# TD4Peripheral.net
KiCad netlist of a schematic drawn in EAGLE
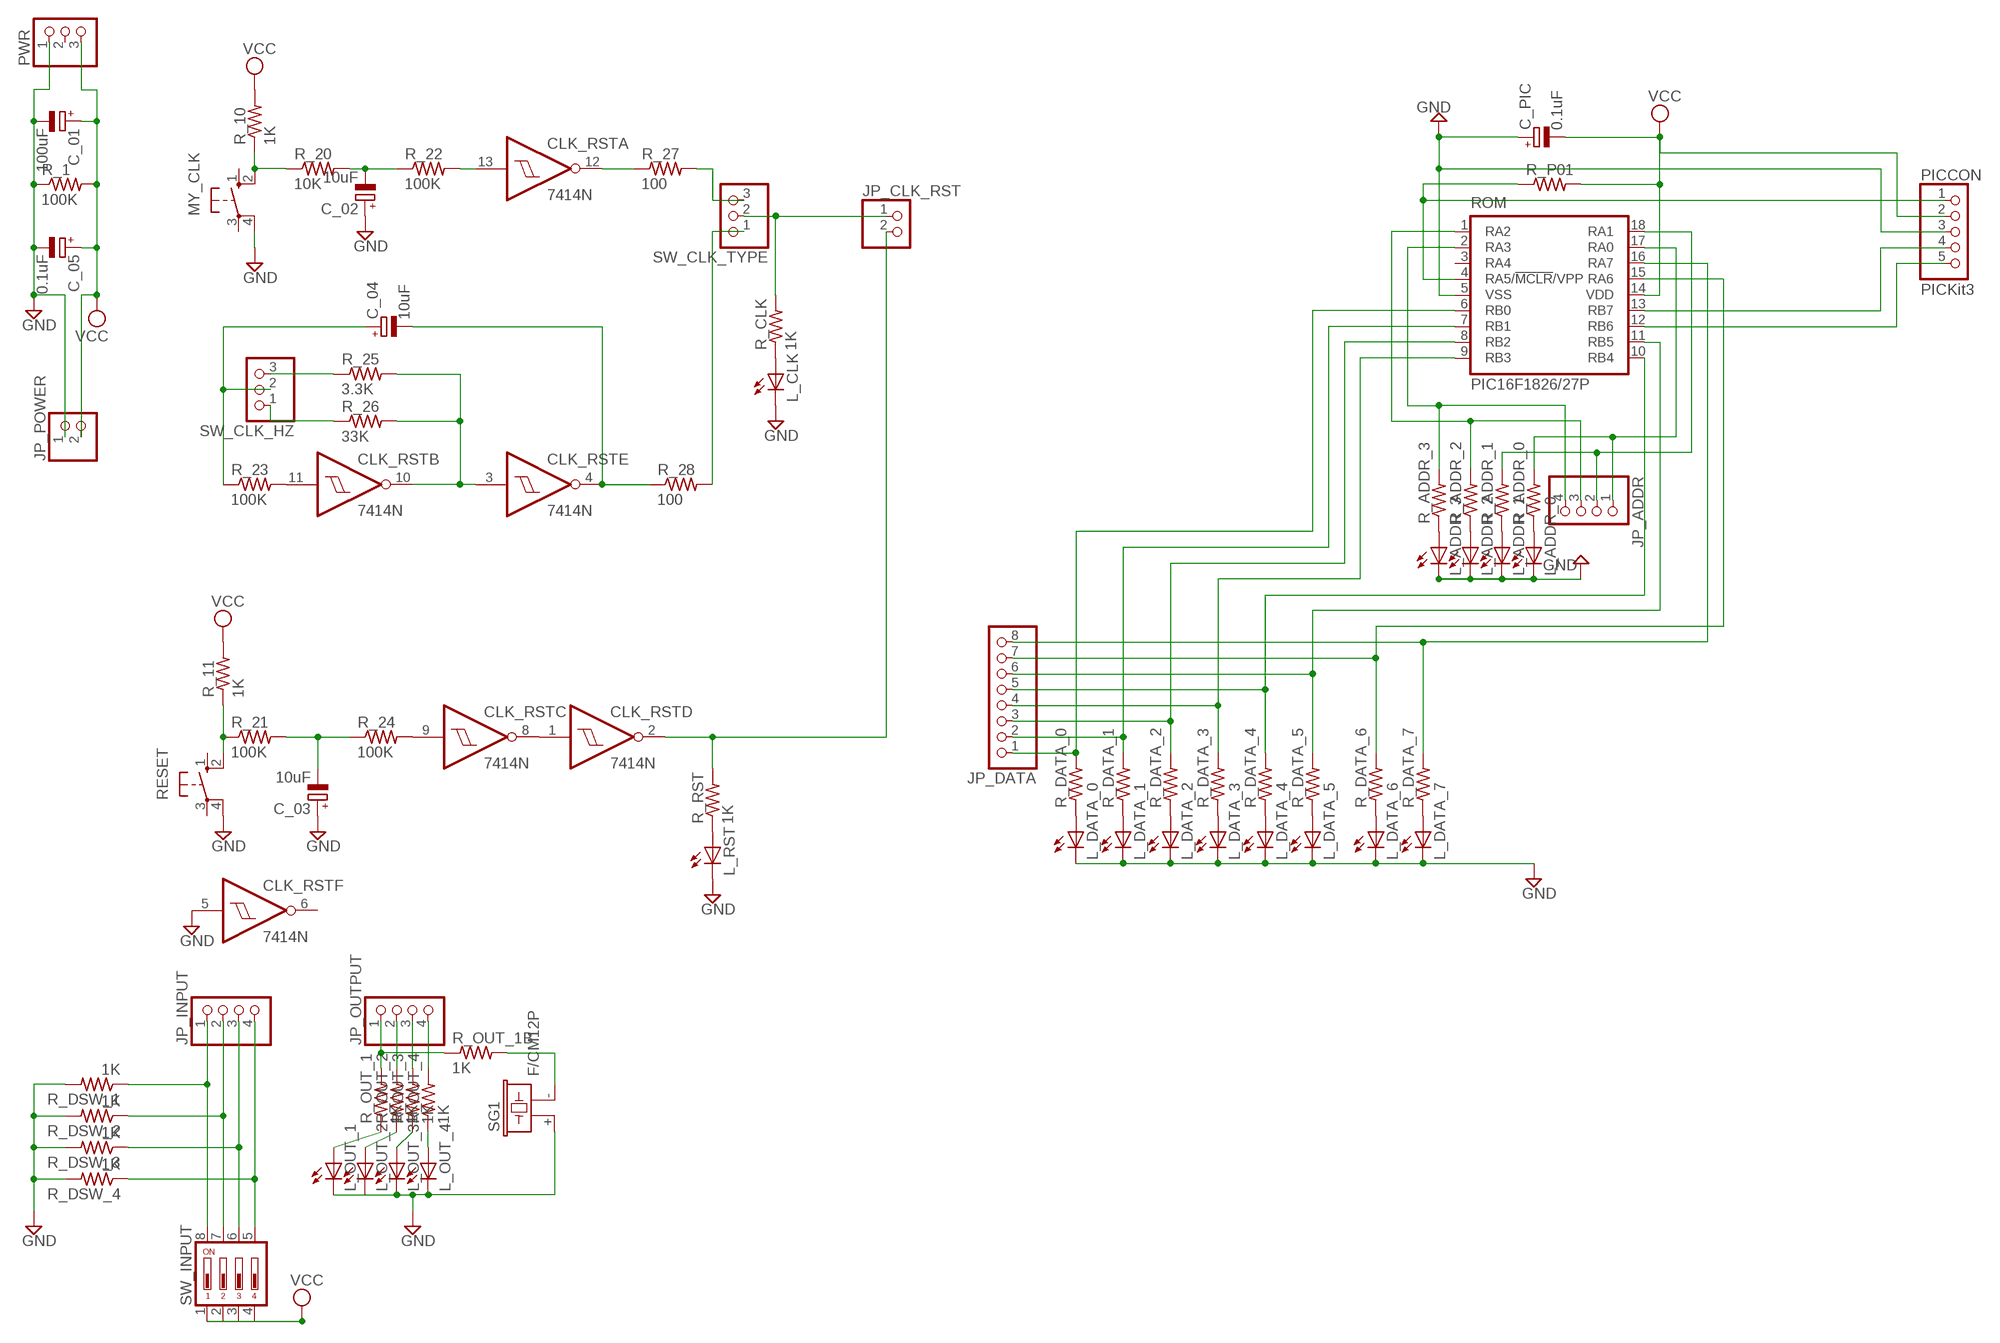
[diagram p0: schematic, sheet 1]

(export (version "E")
  (design (tool "Eeschema 10.0.6"))
  (components
    (comp (ref "CLK_RST")
      (value "7414N")
      (footprint "eagle-import:DIL14")
      (libsource (lib "eagle-import") (part "7414N"))
    )
    (comp (ref "C_01")
      (value "100uF")
      (footprint "eagle-import:E2-5")
      (libsource (lib "eagle-import") (part "CPOL-EUE2-5"))
    )
    (comp (ref "C_02")
      (value "10uF")
      (footprint "eagle-import:E2-5")
      (libsource (lib "eagle-import") (part "CPOL-EUE2-5"))
    )
    (comp (ref "C_03")
      (value "10uF")
      (footprint "eagle-import:E2-5")
      (libsource (lib "eagle-import") (part "CPOL-EUE2-5"))
    )
    (comp (ref "C_04")
      (value "10uF")
      (footprint "eagle-import:E2-5")
      (libsource (lib "eagle-import") (part "CPOL-EUE2-5"))
    )
    (comp (ref "C_05")
      (value "0.1uF")
      (footprint "eagle-import:E2-5")
      (libsource (lib "eagle-import") (part "CPOL-EUE2-5"))
    )
    (comp (ref "C_PIC")
      (value "0.1uF")
      (footprint "eagle-import:E2-5")
      (libsource (lib "eagle-import") (part "CPOL-EUE2-5"))
    )
    (comp (ref "JP_ADDR")
      (value "PINHD-1X4")
      (footprint "eagle-import:1X04")
      (libsource (lib "eagle-import") (part "PINHD-1X4"))
    )
    (comp (ref "JP_CLK_RST")
      (value "PINHD-1X2")
      (footprint "eagle-import:1X02")
      (libsource (lib "eagle-import") (part "PINHD-1X2"))
    )
    (comp (ref "JP_DATA")
      (value "PINHD-1X8")
      (footprint "eagle-import:1X08")
      (libsource (lib "eagle-import") (part "PINHD-1X8"))
    )
    (comp (ref "JP_INPUT")
      (value "PINHD-1X4")
      (footprint "eagle-import:1X04")
      (libsource (lib "eagle-import") (part "PINHD-1X4"))
    )
    (comp (ref "JP_OUTPUT")
      (value "PINHD-1X4")
      (footprint "eagle-import:1X04")
      (libsource (lib "eagle-import") (part "PINHD-1X4"))
    )
    (comp (ref "JP_POWER")
      (value "PINHD-1X2")
      (footprint "eagle-import:1X02")
      (libsource (lib "eagle-import") (part "PINHD-1X2"))
    )
    (comp (ref "L_ADDR_0")
      (value "LED5MM")
      (footprint "eagle-import:LED5MM")
      (libsource (lib "eagle-import") (part "LED5MM"))
    )
    (comp (ref "L_ADDR_1")
      (value "LED5MM")
      (footprint "eagle-import:LED5MM")
      (libsource (lib "eagle-import") (part "LED5MM"))
    )
    (comp (ref "L_ADDR_2")
      (value "LED5MM")
      (footprint "eagle-import:LED5MM")
      (libsource (lib "eagle-import") (part "LED5MM"))
    )
    (comp (ref "L_ADDR_3")
      (value "LED5MM")
      (footprint "eagle-import:LED5MM")
      (libsource (lib "eagle-import") (part "LED5MM"))
    )
    (comp (ref "L_CLK")
      (value "LED5MM")
      (footprint "eagle-import:LED5MM")
      (libsource (lib "eagle-import") (part "LED5MM"))
    )
    (comp (ref "L_DATA_0")
      (value "LED5MM")
      (footprint "eagle-import:LED5MM")
      (libsource (lib "eagle-import") (part "LED5MM"))
    )
    (comp (ref "L_DATA_1")
      (value "LED5MM")
      (footprint "eagle-import:LED5MM")
      (libsource (lib "eagle-import") (part "LED5MM"))
    )
    (comp (ref "L_DATA_2")
      (value "LED5MM")
      (footprint "eagle-import:LED5MM")
      (libsource (lib "eagle-import") (part "LED5MM"))
    )
    (comp (ref "L_DATA_3")
      (value "LED5MM")
      (footprint "eagle-import:LED5MM")
      (libsource (lib "eagle-import") (part "LED5MM"))
    )
    (comp (ref "L_DATA_4")
      (value "LED5MM")
      (footprint "eagle-import:LED5MM")
      (libsource (lib "eagle-import") (part "LED5MM"))
    )
    (comp (ref "L_DATA_5")
      (value "LED5MM")
      (footprint "eagle-import:LED5MM")
      (libsource (lib "eagle-import") (part "LED5MM"))
    )
    (comp (ref "L_DATA_6")
      (value "LED5MM")
      (footprint "eagle-import:LED5MM")
      (libsource (lib "eagle-import") (part "LED5MM"))
    )
    (comp (ref "L_DATA_7")
      (value "LED5MM")
      (footprint "eagle-import:LED5MM")
      (libsource (lib "eagle-import") (part "LED5MM"))
    )
    (comp (ref "L_OUT_1")
      (value "LED5MM")
      (footprint "eagle-import:LED5MM")
      (libsource (lib "eagle-import") (part "LED5MM"))
    )
    (comp (ref "L_OUT_2")
      (value "LED5MM")
      (footprint "eagle-import:LED5MM")
      (libsource (lib "eagle-import") (part "LED5MM"))
    )
    (comp (ref "L_OUT_3")
      (value "LED5MM")
      (footprint "eagle-import:LED5MM")
      (libsource (lib "eagle-import") (part "LED5MM"))
    )
    (comp (ref "L_OUT_4")
      (value "LED5MM")
      (footprint "eagle-import:LED5MM")
      (libsource (lib "eagle-import") (part "LED5MM"))
    )
    (comp (ref "L_RST")
      (value "LED5MM")
      (footprint "eagle-import:LED5MM")
      (libsource (lib "eagle-import") (part "LED5MM"))
    )
    (comp (ref "MY_CLK")
      (value "10-XX")
      (footprint "eagle-import:B3F-10XX")
      (fields (field (name "MPN") "B3F-1000"))
      (libsource (lib "eagle-import") (part "10-XX"))
    )
    (comp (ref "PICCON")
      (value "PICKit3")
      (footprint "eagle-import:1X05")
      (libsource (lib "eagle-import") (part "PINHD-1X5"))
    )
    (comp (ref "PWR")
      (value "PINHD-1X3")
      (footprint "eagle-import:1X03")
      (libsource (lib "eagle-import") (part "PINHD-1X3"))
    )
    (comp (ref "RESET")
      (value "10-XX")
      (footprint "eagle-import:B3F-10XX")
      (fields (field (name "MPN") "B3F-1000"))
      (libsource (lib "eagle-import") (part "10-XX"))
    )
    (comp (ref "ROM")
      (value "PIC16F1826/27P")
      (footprint "eagle-import:DIL18")
      (libsource (lib "eagle-import") (part "PIC16F1826/27P"))
    )
    (comp (ref "R_1")
      (value "100K")
      (footprint "eagle-import:0204_7")
      (libsource (lib "eagle-import") (part "R-US_0204/7"))
    )
    (comp (ref "R_10")
      (value "1K")
      (footprint "eagle-import:0204_7")
      (libsource (lib "eagle-import") (part "R-US_0204/7"))
    )
    (comp (ref "R_11")
      (value "1K")
      (footprint "eagle-import:0204_7")
      (libsource (lib "eagle-import") (part "R-US_0204/7"))
    )
    (comp (ref "R_20")
      (value "10K")
      (footprint "eagle-import:0204_7")
      (libsource (lib "eagle-import") (part "R-US_0204/7"))
    )
    (comp (ref "R_21")
      (value "100K")
      (footprint "eagle-import:0204_7")
      (libsource (lib "eagle-import") (part "R-US_0204/7"))
    )
    (comp (ref "R_22")
      (value "100K")
      (footprint "eagle-import:0204_7")
      (libsource (lib "eagle-import") (part "R-US_0204/7"))
    )
    (comp (ref "R_23")
      (value "100K")
      (footprint "eagle-import:0204_7")
      (libsource (lib "eagle-import") (part "R-US_0204/7"))
    )
    (comp (ref "R_24")
      (value "100K")
      (footprint "eagle-import:0204_7")
      (libsource (lib "eagle-import") (part "R-US_0204/7"))
    )
    (comp (ref "R_25")
      (value "3.3K")
      (footprint "eagle-import:0204_7")
      (libsource (lib "eagle-import") (part "R-US_0204/7"))
    )
    (comp (ref "R_26")
      (value "33K")
      (footprint "eagle-import:0204_7")
      (libsource (lib "eagle-import") (part "R-US_0204/7"))
    )
    (comp (ref "R_27")
      (value "100")
      (footprint "eagle-import:0204_7")
      (libsource (lib "eagle-import") (part "R-US_0204/7"))
    )
    (comp (ref "R_28")
      (value "100")
      (footprint "eagle-import:0204_7")
      (libsource (lib "eagle-import") (part "R-US_0204/7"))
    )
    (comp (ref "R_ADDR_0")
      (value "R-US_0204/7")
      (footprint "eagle-import:0204_7")
      (libsource (lib "eagle-import") (part "R-US_0204/7"))
    )
    (comp (ref "R_ADDR_1")
      (value "R-US_0204/7")
      (footprint "eagle-import:0204_7")
      (libsource (lib "eagle-import") (part "R-US_0204/7"))
    )
    (comp (ref "R_ADDR_2")
      (value "R-US_0204/7")
      (footprint "eagle-import:0204_7")
      (libsource (lib "eagle-import") (part "R-US_0204/7"))
    )
    (comp (ref "R_ADDR_3")
      (value "R-US_0204/7")
      (footprint "eagle-import:0204_7")
      (libsource (lib "eagle-import") (part "R-US_0204/7"))
    )
    (comp (ref "R_CLK")
      (value "1K")
      (footprint "eagle-import:0204_7")
      (libsource (lib "eagle-import") (part "R-US_0204/7"))
    )
    (comp (ref "R_DATA_0")
      (value "R-US_0204/7")
      (footprint "eagle-import:0204_7")
      (libsource (lib "eagle-import") (part "R-US_0204/7"))
    )
    (comp (ref "R_DATA_1")
      (value "R-US_0204/7")
      (footprint "eagle-import:0204_7")
      (libsource (lib "eagle-import") (part "R-US_0204/7"))
    )
    (comp (ref "R_DATA_2")
      (value "R-US_0204/7")
      (footprint "eagle-import:0204_7")
      (libsource (lib "eagle-import") (part "R-US_0204/7"))
    )
    (comp (ref "R_DATA_3")
      (value "R-US_0204/7")
      (footprint "eagle-import:0204_7")
      (libsource (lib "eagle-import") (part "R-US_0204/7"))
    )
    (comp (ref "R_DATA_4")
      (value "R-US_0204/7")
      (footprint "eagle-import:0204_7")
      (libsource (lib "eagle-import") (part "R-US_0204/7"))
    )
    (comp (ref "R_DATA_5")
      (value "R-US_0204/7")
      (footprint "eagle-import:0204_7")
      (libsource (lib "eagle-import") (part "R-US_0204/7"))
    )
    (comp (ref "R_DATA_6")
      (value "R-US_0204/7")
      (footprint "eagle-import:0204_7")
      (libsource (lib "eagle-import") (part "R-US_0204/7"))
    )
    (comp (ref "R_DATA_7")
      (value "R-US_0204/7")
      (footprint "eagle-import:0204_7")
      (libsource (lib "eagle-import") (part "R-US_0204/7"))
    )
    (comp (ref "R_DSW_1")
      (value "1K")
      (footprint "eagle-import:0204_7")
      (libsource (lib "eagle-import") (part "R-US_0204/7"))
    )
    (comp (ref "R_DSW_2")
      (value "1K")
      (footprint "eagle-import:0204_7")
      (libsource (lib "eagle-import") (part "R-US_0204/7"))
    )
    (comp (ref "R_DSW_3")
      (value "1K")
      (footprint "eagle-import:0204_7")
      (libsource (lib "eagle-import") (part "R-US_0204/7"))
    )
    (comp (ref "R_DSW_4")
      (value "1K")
      (footprint "eagle-import:0204_7")
      (libsource (lib "eagle-import") (part "R-US_0204/7"))
    )
    (comp (ref "R_OUT_1")
      (value "1K")
      (footprint "eagle-import:0204_7")
      (libsource (lib "eagle-import") (part "R-US_0204/7"))
    )
    (comp (ref "R_OUT_1B")
      (value "1K")
      (footprint "eagle-import:0204_7")
      (libsource (lib "eagle-import") (part "R-US_0204/7"))
    )
    (comp (ref "R_OUT_2")
      (value "1K")
      (footprint "eagle-import:0204_7")
      (libsource (lib "eagle-import") (part "R-US_0204/7"))
    )
    (comp (ref "R_OUT_3")
      (value "1K")
      (footprint "eagle-import:0204_7")
      (libsource (lib "eagle-import") (part "R-US_0204/7"))
    )
    (comp (ref "R_OUT_4")
      (value "1K")
      (footprint "eagle-import:0204_7")
      (libsource (lib "eagle-import") (part "R-US_0204/7"))
    )
    (comp (ref "R_P01")
      (value "R-US_0204/7")
      (footprint "eagle-import:0204_7")
      (libsource (lib "eagle-import") (part "R-US_0204/7"))
    )
    (comp (ref "R_RST")
      (value "1K")
      (footprint "eagle-import:0204_7")
      (libsource (lib "eagle-import") (part "R-US_0204/7"))
    )
    (comp (ref "SG1")
      (value "F/CM12P")
      (footprint "eagle-import:F_CM12P")
      (libsource (lib "eagle-import") (part "F/CM12P"))
    )
    (comp (ref "SW_CLK_HZ")
      (value "PINHD-1X3")
      (footprint "eagle-import:1X03")
      (libsource (lib "eagle-import") (part "PINHD-1X3"))
    )
    (comp (ref "SW_CLK_TYPE")
      (value "PINHD-1X3")
      (footprint "eagle-import:1X03")
      (libsource (lib "eagle-import") (part "PINHD-1X3"))
    )
    (comp (ref "SW_INPUT")
      (value "DP04")
      (footprint "eagle-import:DP-04")
      (libsource (lib "eagle-import") (part "DP04"))
    )
  )
  (nets
    (net (code "1") (name "GND") (class "Default")
      (node (ref "CLK_RST") (pin "5") (pinfunction "I_5") (pintype "input"))
      (node (ref "C_01") (pin "-") (pinfunction "-_-") (pintype "passive"))
      (node (ref "C_02") (pin "+") (pinfunction "+_+") (pintype "passive"))
      (node (ref "C_03") (pin "+") (pinfunction "+_+") (pintype "passive"))
      (node (ref "C_05") (pin "-") (pinfunction "-_-") (pintype "passive"))
      (node (ref "C_PIC") (pin "+") (pinfunction "+_+") (pintype "passive"))
      (node (ref "JP_POWER") (pin "1") (pinfunction "1_1") (pintype "passive"))
      (node (ref "L_ADDR_0") (pin "K") (pinfunction "C_K") (pintype "passive"))
      (node (ref "L_ADDR_1") (pin "K") (pinfunction "C_K") (pintype "passive"))
      (node (ref "L_ADDR_2") (pin "K") (pinfunction "C_K") (pintype "passive"))
      (node (ref "L_ADDR_3") (pin "K") (pinfunction "C_K") (pintype "passive"))
      (node (ref "L_CLK") (pin "K") (pinfunction "C_K") (pintype "passive"))
      (node (ref "L_DATA_0") (pin "K") (pinfunction "C_K") (pintype "passive"))
      (node (ref "L_DATA_1") (pin "K") (pinfunction "C_K") (pintype "passive"))
      (node (ref "L_DATA_2") (pin "K") (pinfunction "C_K") (pintype "passive"))
      (node (ref "L_DATA_3") (pin "K") (pinfunction "C_K") (pintype "passive"))
      (node (ref "L_DATA_4") (pin "K") (pinfunction "C_K") (pintype "passive"))
      (node (ref "L_DATA_5") (pin "K") (pinfunction "C_K") (pintype "passive"))
      (node (ref "L_DATA_6") (pin "K") (pinfunction "C_K") (pintype "passive"))
      (node (ref "L_DATA_7") (pin "K") (pinfunction "C_K") (pintype "passive"))
      (node (ref "L_OUT_1") (pin "K") (pinfunction "C_K") (pintype "passive"))
      (node (ref "L_OUT_2") (pin "K") (pinfunction "C_K") (pintype "passive"))
      (node (ref "L_OUT_3") (pin "K") (pinfunction "C_K") (pintype "passive"))
      (node (ref "L_OUT_4") (pin "K") (pinfunction "C_K") (pintype "passive"))
      (node (ref "L_RST") (pin "K") (pinfunction "C_K") (pintype "passive"))
      (node (ref "MY_CLK") (pin "4") (pinfunction "P1_4") (pintype "passive"))
      (node (ref "PICCON") (pin "3") (pinfunction "3_3") (pintype "passive"))
      (node (ref "PWR") (pin "1") (pinfunction "1_1") (pintype "passive"))
      (node (ref "RESET") (pin "4") (pinfunction "P1_4") (pintype "passive"))
      (node (ref "ROM") (pin "5") (pinfunction "VSS_5") (pintype "power_in"))
      (node (ref "R_1") (pin "1") (pinfunction "1_1") (pintype "passive"))
      (node (ref "R_DSW_1") (pin "2") (pinfunction "2_2") (pintype "passive"))
      (node (ref "R_DSW_2") (pin "2") (pinfunction "2_2") (pintype "passive"))
      (node (ref "R_DSW_3") (pin "2") (pinfunction "2_2") (pintype "passive"))
      (node (ref "R_DSW_4") (pin "2") (pinfunction "2_2") (pintype "passive"))
      (node (ref "SG1") (pin "+") (pinfunction "1_+") (pintype "passive"))
    )
    (net (code "2") (name "Net-(CLK_RSTA-I)") (class "Default")
      (node (ref "CLK_RST") (pin "13") (pinfunction "I_13") (pintype "input"))
      (node (ref "R_22") (pin "2") (pinfunction "2_2") (pintype "passive"))
    )
    (net (code "3") (name "Net-(CLK_RSTA-O)") (class "Default")
      (node (ref "CLK_RST") (pin "12") (pinfunction "O_12") (pintype "output"))
      (node (ref "R_27") (pin "1") (pinfunction "1_1") (pintype "passive"))
    )
    (net (code "4") (name "Net-(CLK_RSTB-I)") (class "Default")
      (node (ref "CLK_RST") (pin "11") (pinfunction "I_11") (pintype "input"))
      (node (ref "R_23") (pin "2") (pinfunction "2_2") (pintype "passive"))
    )
    (net (code "5") (name "Net-(CLK_RSTB-O)") (class "Default")
      (node (ref "CLK_RST") (pin "10") (pinfunction "O_10") (pintype "output"))
      (node (ref "CLK_RST") (pin "3") (pinfunction "I_3") (pintype "input"))
      (node (ref "R_25") (pin "2") (pinfunction "2_2") (pintype "passive"))
      (node (ref "R_26") (pin "2") (pinfunction "2_2") (pintype "passive"))
    )
    (net (code "6") (name "Net-(CLK_RSTC-I)") (class "Default")
      (node (ref "CLK_RST") (pin "9") (pinfunction "I_9") (pintype "input"))
      (node (ref "R_24") (pin "2") (pinfunction "2_2") (pintype "passive"))
    )
    (net (code "7") (name "Net-(CLK_RSTC-O)") (class "Default")
      (node (ref "CLK_RST") (pin "1") (pinfunction "I_1") (pintype "input"))
      (node (ref "CLK_RST") (pin "8") (pinfunction "O_8") (pintype "output"))
    )
    (net (code "8") (name "Net-(CLK_RSTD-O)") (class "Default")
      (node (ref "CLK_RST") (pin "2") (pinfunction "O_2") (pintype "output"))
      (node (ref "JP_CLK_RST") (pin "2") (pinfunction "2_2") (pintype "passive"))
      (node (ref "R_RST") (pin "2") (pinfunction "2_2") (pintype "passive"))
    )
    (net (code "9") (name "Net-(CLK_RSTE-O)") (class "Default")
      (node (ref "CLK_RST") (pin "4") (pinfunction "O_4") (pintype "output"))
      (node (ref "C_04") (pin "-") (pinfunction "-_-") (pintype "passive"))
      (node (ref "R_28") (pin "1") (pinfunction "1_1") (pintype "passive"))
    )
    (net (code "10") (name "Net-(C_02-Pad-)") (class "Default")
      (node (ref "C_02") (pin "-") (pinfunction "-_-") (pintype "passive"))
      (node (ref "R_20") (pin "2") (pinfunction "2_2") (pintype "passive"))
      (node (ref "R_22") (pin "1") (pinfunction "1_1") (pintype "passive"))
    )
    (net (code "11") (name "Net-(C_03-Pad-)") (class "Default")
      (node (ref "C_03") (pin "-") (pinfunction "-_-") (pintype "passive"))
      (node (ref "R_21") (pin "2") (pinfunction "2_2") (pintype "passive"))
      (node (ref "R_24") (pin "1") (pinfunction "1_1") (pintype "passive"))
    )
    (net (code "12") (name "Net-(C_04-Pad+)") (class "Default")
      (node (ref "C_04") (pin "+") (pinfunction "+_+") (pintype "passive"))
      (node (ref "R_23") (pin "1") (pinfunction "1_1") (pintype "passive"))
      (node (ref "SW_CLK_HZ") (pin "2") (pinfunction "2_2") (pintype "passive"))
    )
    (net (code "13") (name "Net-(JP_CLK_RST-Pad1)") (class "Default")
      (node (ref "JP_CLK_RST") (pin "1") (pinfunction "1_1") (pintype "passive"))
      (node (ref "R_CLK") (pin "2") (pinfunction "2_2") (pintype "passive"))
      (node (ref "SW_CLK_TYPE") (pin "2") (pinfunction "2_2") (pintype "passive"))
    )
    (net (code "14") (name "Net-(JP_INPUT-Pad1)") (class "Default")
      (node (ref "JP_INPUT") (pin "1") (pinfunction "1_1") (pintype "passive"))
      (node (ref "R_DSW_1") (pin "1") (pinfunction "1_1") (pintype "passive"))
      (node (ref "SW_INPUT") (pin "8") (pinfunction "8_8") (pintype "passive"))
    )
    (net (code "15") (name "Net-(JP_INPUT-Pad2)") (class "Default")
      (node (ref "JP_INPUT") (pin "2") (pinfunction "2_2") (pintype "passive"))
      (node (ref "R_DSW_2") (pin "1") (pinfunction "1_1") (pintype "passive"))
      (node (ref "SW_INPUT") (pin "7") (pinfunction "7_7") (pintype "passive"))
    )
    (net (code "16") (name "Net-(JP_INPUT-Pad3)") (class "Default")
      (node (ref "JP_INPUT") (pin "3") (pinfunction "3_3") (pintype "passive"))
      (node (ref "R_DSW_3") (pin "1") (pinfunction "1_1") (pintype "passive"))
      (node (ref "SW_INPUT") (pin "6") (pinfunction "6_6") (pintype "passive"))
    )
    (net (code "17") (name "Net-(JP_INPUT-Pad4)") (class "Default")
      (node (ref "JP_INPUT") (pin "4") (pinfunction "4_4") (pintype "passive"))
      (node (ref "R_DSW_4") (pin "1") (pinfunction "1_1") (pintype "passive"))
      (node (ref "SW_INPUT") (pin "5") (pinfunction "5_5") (pintype "passive"))
    )
    (net (code "18") (name "Net-(JP_OUTPUT-Pad1)") (class "Default")
      (node (ref "JP_OUTPUT") (pin "1") (pinfunction "1_1") (pintype "passive"))
      (node (ref "R_OUT_1") (pin "2") (pinfunction "2_2") (pintype "passive"))
      (node (ref "R_OUT_1B") (pin "1") (pinfunction "1_1") (pintype "passive"))
    )
    (net (code "19") (name "Net-(JP_OUTPUT-Pad2)") (class "Default")
      (node (ref "JP_OUTPUT") (pin "2") (pinfunction "2_2") (pintype "passive"))
      (node (ref "R_OUT_2") (pin "2") (pinfunction "2_2") (pintype "passive"))
    )
    (net (code "20") (name "Net-(JP_OUTPUT-Pad3)") (class "Default")
      (node (ref "JP_OUTPUT") (pin "3") (pinfunction "3_3") (pintype "passive"))
      (node (ref "R_OUT_3") (pin "2") (pinfunction "2_2") (pintype "passive"))
    )
    (net (code "21") (name "Net-(JP_OUTPUT-Pad4)") (class "Default")
      (node (ref "JP_OUTPUT") (pin "4") (pinfunction "4_4") (pintype "passive"))
      (node (ref "R_OUT_4") (pin "2") (pinfunction "2_2") (pintype "passive"))
    )
    (net (code "22") (name "Net-(L_ADDR_0-PadA)") (class "Default")
      (node (ref "L_ADDR_0") (pin "A") (pinfunction "A_A") (pintype "passive"))
      (node (ref "R_ADDR_0") (pin "1") (pinfunction "1_1") (pintype "passive"))
    )
    (net (code "23") (name "Net-(L_ADDR_1-PadA)") (class "Default")
      (node (ref "L_ADDR_1") (pin "A") (pinfunction "A_A") (pintype "passive"))
      (node (ref "R_ADDR_1") (pin "1") (pinfunction "1_1") (pintype "passive"))
    )
    (net (code "24") (name "Net-(L_ADDR_2-PadA)") (class "Default")
      (node (ref "L_ADDR_2") (pin "A") (pinfunction "A_A") (pintype "passive"))
      (node (ref "R_ADDR_2") (pin "1") (pinfunction "1_1") (pintype "passive"))
    )
    (net (code "25") (name "Net-(L_ADDR_3-PadA)") (class "Default")
      (node (ref "L_ADDR_3") (pin "A") (pinfunction "A_A") (pintype "passive"))
      (node (ref "R_ADDR_3") (pin "1") (pinfunction "1_1") (pintype "passive"))
    )
    (net (code "26") (name "Net-(L_CLK-PadA)") (class "Default")
      (node (ref "L_CLK") (pin "A") (pinfunction "A_A") (pintype "passive"))
      (node (ref "R_CLK") (pin "1") (pinfunction "1_1") (pintype "passive"))
    )
    (net (code "27") (name "Net-(L_DATA_0-PadA)") (class "Default")
      (node (ref "L_DATA_0") (pin "A") (pinfunction "A_A") (pintype "passive"))
      (node (ref "R_DATA_0") (pin "1") (pinfunction "1_1") (pintype "passive"))
    )
    (net (code "28") (name "Net-(L_DATA_1-PadA)") (class "Default")
      (node (ref "L_DATA_1") (pin "A") (pinfunction "A_A") (pintype "passive"))
      (node (ref "R_DATA_1") (pin "1") (pinfunction "1_1") (pintype "passive"))
    )
    (net (code "29") (name "Net-(L_DATA_2-PadA)") (class "Default")
      (node (ref "L_DATA_2") (pin "A") (pinfunction "A_A") (pintype "passive"))
      (node (ref "R_DATA_2") (pin "1") (pinfunction "1_1") (pintype "passive"))
    )
    (net (code "30") (name "Net-(L_DATA_3-PadA)") (class "Default")
      (node (ref "L_DATA_3") (pin "A") (pinfunction "A_A") (pintype "passive"))
      (node (ref "R_DATA_3") (pin "1") (pinfunction "1_1") (pintype "passive"))
    )
    (net (code "31") (name "Net-(L_DATA_4-PadA)") (class "Default")
      (node (ref "L_DATA_4") (pin "A") (pinfunction "A_A") (pintype "passive"))
      (node (ref "R_DATA_4") (pin "1") (pinfunction "1_1") (pintype "passive"))
    )
    (net (code "32") (name "Net-(L_DATA_5-PadA)") (class "Default")
      (node (ref "L_DATA_5") (pin "A") (pinfunction "A_A") (pintype "passive"))
      (node (ref "R_DATA_5") (pin "1") (pinfunction "1_1") (pintype "passive"))
    )
    (net (code "33") (name "Net-(L_DATA_6-PadA)") (class "Default")
      (node (ref "L_DATA_6") (pin "A") (pinfunction "A_A") (pintype "passive"))
      (node (ref "R_DATA_6") (pin "1") (pinfunction "1_1") (pintype "passive"))
    )
    (net (code "34") (name "Net-(L_DATA_7-PadA)") (class "Default")
      (node (ref "L_DATA_7") (pin "A") (pinfunction "A_A") (pintype "passive"))
      (node (ref "R_DATA_7") (pin "1") (pinfunction "1_1") (pintype "passive"))
    )
    (net (code "35") (name "Net-(L_OUT_1-PadA)") (class "Default")
      (node (ref "L_OUT_1") (pin "A") (pinfunction "A_A") (pintype "passive"))
      (node (ref "R_OUT_1") (pin "1") (pinfunction "1_1") (pintype "passive"))
    )
    (net (code "36") (name "Net-(L_OUT_2-PadA)") (class "Default")
      (node (ref "L_OUT_2") (pin "A") (pinfunction "A_A") (pintype "passive"))
      (node (ref "R_OUT_2") (pin "1") (pinfunction "1_1") (pintype "passive"))
    )
    (net (code "37") (name "Net-(L_OUT_3-PadA)") (class "Default")
      (node (ref "L_OUT_3") (pin "A") (pinfunction "A_A") (pintype "passive"))
      (node (ref "R_OUT_3") (pin "1") (pinfunction "1_1") (pintype "passive"))
    )
    (net (code "38") (name "Net-(L_OUT_4-PadA)") (class "Default")
      (node (ref "L_OUT_4") (pin "A") (pinfunction "A_A") (pintype "passive"))
      (node (ref "R_OUT_4") (pin "1") (pinfunction "1_1") (pintype "passive"))
    )
    (net (code "39") (name "Net-(L_RST-PadA)") (class "Default")
      (node (ref "L_RST") (pin "A") (pinfunction "A_A") (pintype "passive"))
      (node (ref "R_RST") (pin "1") (pinfunction "1_1") (pintype "passive"))
    )
    (net (code "40") (name "Net-(MY_CLK-S1)") (class "Default")
      (node (ref "MY_CLK") (pin "2") (pinfunction "S1_2") (pintype "passive"))
      (node (ref "R_10") (pin "1") (pinfunction "1_1") (pintype "passive"))
      (node (ref "R_20") (pin "1") (pinfunction "1_1") (pintype "passive"))
    )
    (net (code "41") (name "Net-(RESET-S1)") (class "Default")
      (node (ref "RESET") (pin "2") (pinfunction "S1_2") (pintype "passive"))
      (node (ref "R_11") (pin "1") (pinfunction "1_1") (pintype "passive"))
      (node (ref "R_21") (pin "1") (pinfunction "1_1") (pintype "passive"))
    )
    (net (code "42") (name "Net-(ROM-RA0)") (class "Default")
      (node (ref "JP_ADDR") (pin "1") (pinfunction "1_1") (pintype "passive"))
      (node (ref "ROM") (pin "17") (pinfunction "RA0_17") (pintype "bidirectional"))
      (node (ref "R_ADDR_0") (pin "2") (pinfunction "2_2") (pintype "passive"))
    )
    (net (code "43") (name "Net-(ROM-RA1)") (class "Default")
      (node (ref "JP_ADDR") (pin "2") (pinfunction "2_2") (pintype "passive"))
      (node (ref "ROM") (pin "18") (pinfunction "RA1_18") (pintype "bidirectional"))
      (node (ref "R_ADDR_1") (pin "2") (pinfunction "2_2") (pintype "passive"))
    )
    (net (code "44") (name "Net-(ROM-RA2)") (class "Default")
      (node (ref "JP_ADDR") (pin "3") (pinfunction "3_3") (pintype "passive"))
      (node (ref "ROM") (pin "1") (pinfunction "RA2_1") (pintype "bidirectional"))
      (node (ref "R_ADDR_2") (pin "2") (pinfunction "2_2") (pintype "passive"))
    )
    (net (code "45") (name "Net-(ROM-RA3)") (class "Default")
      (node (ref "JP_ADDR") (pin "4") (pinfunction "4_4") (pintype "passive"))
      (node (ref "ROM") (pin "2") (pinfunction "RA3_2") (pintype "bidirectional"))
      (node (ref "R_ADDR_3") (pin "2") (pinfunction "2_2") (pintype "passive"))
    )
    (net (code "46") (name "Net-(ROM-RA5{slash}~{MCLR}{slash}VPP)") (class "Default")
      (node (ref "PICCON") (pin "1") (pinfunction "1_1") (pintype "passive"))
      (node (ref "ROM") (pin "4") (pinfunction "RA5/~{MCLR}/VPP_4") (pintype "bidirectional"))
      (node (ref "R_P01") (pin "1") (pinfunction "1_1") (pintype "passive"))
    )
    (net (code "47") (name "Net-(ROM-RA6)") (class "Default")
      (node (ref "JP_DATA") (pin "7") (pinfunction "7_7") (pintype "passive"))
      (node (ref "ROM") (pin "15") (pinfunction "RA6_15") (pintype "bidirectional"))
      (node (ref "R_DATA_6") (pin "2") (pinfunction "2_2") (pintype "passive"))
    )
    (net (code "48") (name "Net-(ROM-RA7)") (class "Default")
      (node (ref "JP_DATA") (pin "8") (pinfunction "8_8") (pintype "passive"))
      (node (ref "ROM") (pin "16") (pinfunction "RA7_16") (pintype "bidirectional"))
      (node (ref "R_DATA_7") (pin "2") (pinfunction "2_2") (pintype "passive"))
    )
    (net (code "49") (name "Net-(ROM-RB0)") (class "Default")
      (node (ref "JP_DATA") (pin "1") (pinfunction "1_1") (pintype "passive"))
      (node (ref "ROM") (pin "6") (pinfunction "RB0_6") (pintype "bidirectional"))
      (node (ref "R_DATA_0") (pin "2") (pinfunction "2_2") (pintype "passive"))
    )
    (net (code "50") (name "Net-(ROM-RB1)") (class "Default")
      (node (ref "JP_DATA") (pin "2") (pinfunction "2_2") (pintype "passive"))
      (node (ref "ROM") (pin "7") (pinfunction "RB1_7") (pintype "bidirectional"))
      (node (ref "R_DATA_1") (pin "2") (pinfunction "2_2") (pintype "passive"))
    )
    (net (code "51") (name "Net-(ROM-RB2)") (class "Default")
      (node (ref "JP_DATA") (pin "3") (pinfunction "3_3") (pintype "passive"))
      (node (ref "ROM") (pin "8") (pinfunction "RB2_8") (pintype "bidirectional"))
      (node (ref "R_DATA_2") (pin "2") (pinfunction "2_2") (pintype "passive"))
    )
    (net (code "52") (name "Net-(ROM-RB3)") (class "Default")
      (node (ref "JP_DATA") (pin "4") (pinfunction "4_4") (pintype "passive"))
      (node (ref "ROM") (pin "9") (pinfunction "RB3_9") (pintype "bidirectional"))
      (node (ref "R_DATA_3") (pin "2") (pinfunction "2_2") (pintype "passive"))
    )
    (net (code "53") (name "Net-(ROM-RB4)") (class "Default")
      (node (ref "JP_DATA") (pin "5") (pinfunction "5_5") (pintype "passive"))
      (node (ref "ROM") (pin "10") (pinfunction "RB4_10") (pintype "bidirectional"))
      (node (ref "R_DATA_4") (pin "2") (pinfunction "2_2") (pintype "passive"))
    )
    (net (code "54") (name "Net-(ROM-RB5)") (class "Default")
      (node (ref "JP_DATA") (pin "6") (pinfunction "6_6") (pintype "passive"))
      (node (ref "ROM") (pin "11") (pinfunction "RB5_11") (pintype "bidirectional"))
      (node (ref "R_DATA_5") (pin "2") (pinfunction "2_2") (pintype "passive"))
    )
    (net (code "55") (name "Net-(ROM-RB6)") (class "Default")
      (node (ref "PICCON") (pin "5") (pinfunction "5_5") (pintype "passive"))
      (node (ref "ROM") (pin "12") (pinfunction "RB6_12") (pintype "bidirectional"))
    )
    (net (code "56") (name "Net-(ROM-RB7)") (class "Default")
      (node (ref "PICCON") (pin "4") (pinfunction "4_4") (pintype "passive"))
      (node (ref "ROM") (pin "13") (pinfunction "RB7_13") (pintype "bidirectional"))
    )
    (net (code "57") (name "Net-(R_25-Pad1)") (class "Default")
      (node (ref "R_25") (pin "1") (pinfunction "1_1") (pintype "passive"))
      (node (ref "SW_CLK_HZ") (pin "3") (pinfunction "3_3") (pintype "passive"))
    )
    (net (code "58") (name "Net-(R_26-Pad1)") (class "Default")
      (node (ref "R_26") (pin "1") (pinfunction "1_1") (pintype "passive"))
      (node (ref "SW_CLK_HZ") (pin "1") (pinfunction "1_1") (pintype "passive"))
    )
    (net (code "59") (name "Net-(R_27-Pad2)") (class "Default")
      (node (ref "R_27") (pin "2") (pinfunction "2_2") (pintype "passive"))
      (node (ref "SW_CLK_TYPE") (pin "3") (pinfunction "3_3") (pintype "passive"))
    )
    (net (code "60") (name "Net-(R_28-Pad2)") (class "Default")
      (node (ref "R_28") (pin "2") (pinfunction "2_2") (pintype "passive"))
      (node (ref "SW_CLK_TYPE") (pin "1") (pinfunction "1_1") (pintype "passive"))
    )
    (net (code "61") (name "Net-(SG1-2)") (class "Default")
      (node (ref "R_OUT_1B") (pin "2") (pinfunction "2_2") (pintype "passive"))
      (node (ref "SG1") (pin "-") (pinfunction "2_-") (pintype "passive"))
    )
    (net (code "62") (name "VCC") (class "Default")
      (node (ref "C_01") (pin "+") (pinfunction "+_+") (pintype "passive"))
      (node (ref "C_05") (pin "+") (pinfunction "+_+") (pintype "passive"))
      (node (ref "C_PIC") (pin "-") (pinfunction "-_-") (pintype "passive"))
      (node (ref "JP_POWER") (pin "2") (pinfunction "2_2") (pintype "passive"))
      (node (ref "PICCON") (pin "2") (pinfunction "2_2") (pintype "passive"))
      (node (ref "PWR") (pin "3") (pinfunction "3_3") (pintype "passive"))
      (node (ref "ROM") (pin "14") (pinfunction "VDD_14") (pintype "power_in"))
      (node (ref "R_1") (pin "2") (pinfunction "2_2") (pintype "passive"))
      (node (ref "R_10") (pin "2") (pinfunction "2_2") (pintype "passive"))
      (node (ref "R_11") (pin "2") (pinfunction "2_2") (pintype "passive"))
      (node (ref "R_P01") (pin "2") (pinfunction "2_2") (pintype "passive"))
      (node (ref "SW_INPUT") (pin "1") (pinfunction "1_1") (pintype "passive"))
      (node (ref "SW_INPUT") (pin "2") (pinfunction "2_2") (pintype "passive"))
      (node (ref "SW_INPUT") (pin "3") (pinfunction "3_3") (pintype "passive"))
      (node (ref "SW_INPUT") (pin "4") (pinfunction "4_4") (pintype "passive"))
    )
    (net (code "63") (name "unconnected-(CLK_RSTF-O-Pad6)") (class "Default")
      (node (ref "CLK_RST") (pin "6") (pinfunction "O_6") (pintype "output"))
    )
    (net (code "64") (name "unconnected-(MY_CLK-P-Pad3)") (class "Default")
      (node (ref "MY_CLK") (pin "3") (pinfunction "P_3") (pintype "passive"))
    )
    (net (code "65") (name "unconnected-(MY_CLK-S-Pad1)") (class "Default")
      (node (ref "MY_CLK") (pin "1") (pinfunction "S_1") (pintype "passive"))
    )
    (net (code "66") (name "unconnected-(PWR-Pad2)") (class "Default")
      (node (ref "PWR") (pin "2") (pinfunction "2_2") (pintype "passive"))
    )
    (net (code "67") (name "unconnected-(RESET-P-Pad3)") (class "Default")
      (node (ref "RESET") (pin "3") (pinfunction "P_3") (pintype "passive"))
    )
    (net (code "68") (name "unconnected-(RESET-S-Pad1)") (class "Default")
      (node (ref "RESET") (pin "1") (pinfunction "S_1") (pintype "passive"))
    )
    (net (code "69") (name "unconnected-(ROM-RA4-Pad3)") (class "Default")
      (node (ref "ROM") (pin "3") (pinfunction "RA4_3") (pintype "bidirectional"))
    )
  )
)
